# 2uprava2.net
KiCad netlist of a schematic drawn in EAGLE
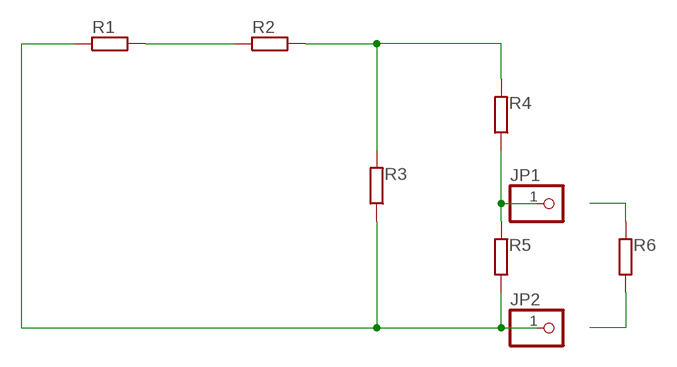
[diagram p0: schematic, sheet 1]

(export (version "E")
  (design (tool "Eeschema 10.0.6"))
  (components
    (comp (ref "JP1")
      (value "PINHD-1X1")
      (footprint "eagle-import:1X01")
      (libsource (lib "eagle-import") (part "PINHD-1X1"))
    )
    (comp (ref "JP2")
      (value "PINHD-1X1")
      (footprint "eagle-import:1X01")
      (libsource (lib "eagle-import") (part "PINHD-1X1"))
    )
    (comp (ref "R1")
      (value "50R")
      (footprint "eagle-import:0204_7")
      (libsource (lib "eagle-import") (part "R-EU_0204/7"))
    )
    (comp (ref "R2")
      (value "310R")
      (footprint "eagle-import:0204_7")
      (libsource (lib "eagle-import") (part "R-EU_0204/7"))
    )
    (comp (ref "R3")
      (value "610R")
      (footprint "eagle-import:0204_7")
      (libsource (lib "eagle-import") (part "R-EU_0204/7"))
    )
    (comp (ref "R4")
      (value "220R")
      (footprint "eagle-import:0204_7")
      (libsource (lib "eagle-import") (part "R-EU_0204/7"))
    )
    (comp (ref "R5")
      (value "570R")
      (footprint "eagle-import:0204_7")
      (libsource (lib "eagle-import") (part "R-EU_0204/7"))
    )
    (comp (ref "R6")
      (value "200R")
      (footprint "eagle-import:0204_7")
      (libsource (lib "eagle-import") (part "R-EU_0204/7"))
    )
  )
  (nets
    (net (code "1") (name "Net-(JP1-Pad1)") (class "Default")
      (node (ref "JP1") (pin "1") (pinfunction "1_1") (pintype "passive"))
      (node (ref "R4") (pin "1") (pinfunction "1_1") (pintype "passive"))
      (node (ref "R5") (pin "2") (pinfunction "2_2") (pintype "passive"))
    )
    (net (code "2") (name "Net-(JP2-Pad1)") (class "Default")
      (node (ref "JP2") (pin "1") (pinfunction "1_1") (pintype "passive"))
      (node (ref "R1") (pin "1") (pinfunction "1_1") (pintype "passive"))
      (node (ref "R3") (pin "1") (pinfunction "1_1") (pintype "passive"))
      (node (ref "R5") (pin "1") (pinfunction "1_1") (pintype "passive"))
    )
    (net (code "3") (name "Net-(R1-Pad2)") (class "Default")
      (node (ref "R1") (pin "2") (pinfunction "2_2") (pintype "passive"))
      (node (ref "R2") (pin "1") (pinfunction "1_1") (pintype "passive"))
    )
    (net (code "4") (name "Net-(R2-Pad2)") (class "Default")
      (node (ref "R2") (pin "2") (pinfunction "2_2") (pintype "passive"))
      (node (ref "R3") (pin "2") (pinfunction "2_2") (pintype "passive"))
      (node (ref "R4") (pin "2") (pinfunction "2_2") (pintype "passive"))
    )
    (net (code "5") (name "unconnected-(R6-Pad1)") (class "Default")
      (node (ref "R6") (pin "1") (pinfunction "1_1") (pintype "passive"))
    )
    (net (code "6") (name "unconnected-(R6-Pad2)") (class "Default")
      (node (ref "R6") (pin "2") (pinfunction "2_2") (pintype "passive"))
    )
  )
)
